# STM32G4_4008_brushless_motor.net
KiCad netlist of a schematic drawn in Altium Designer
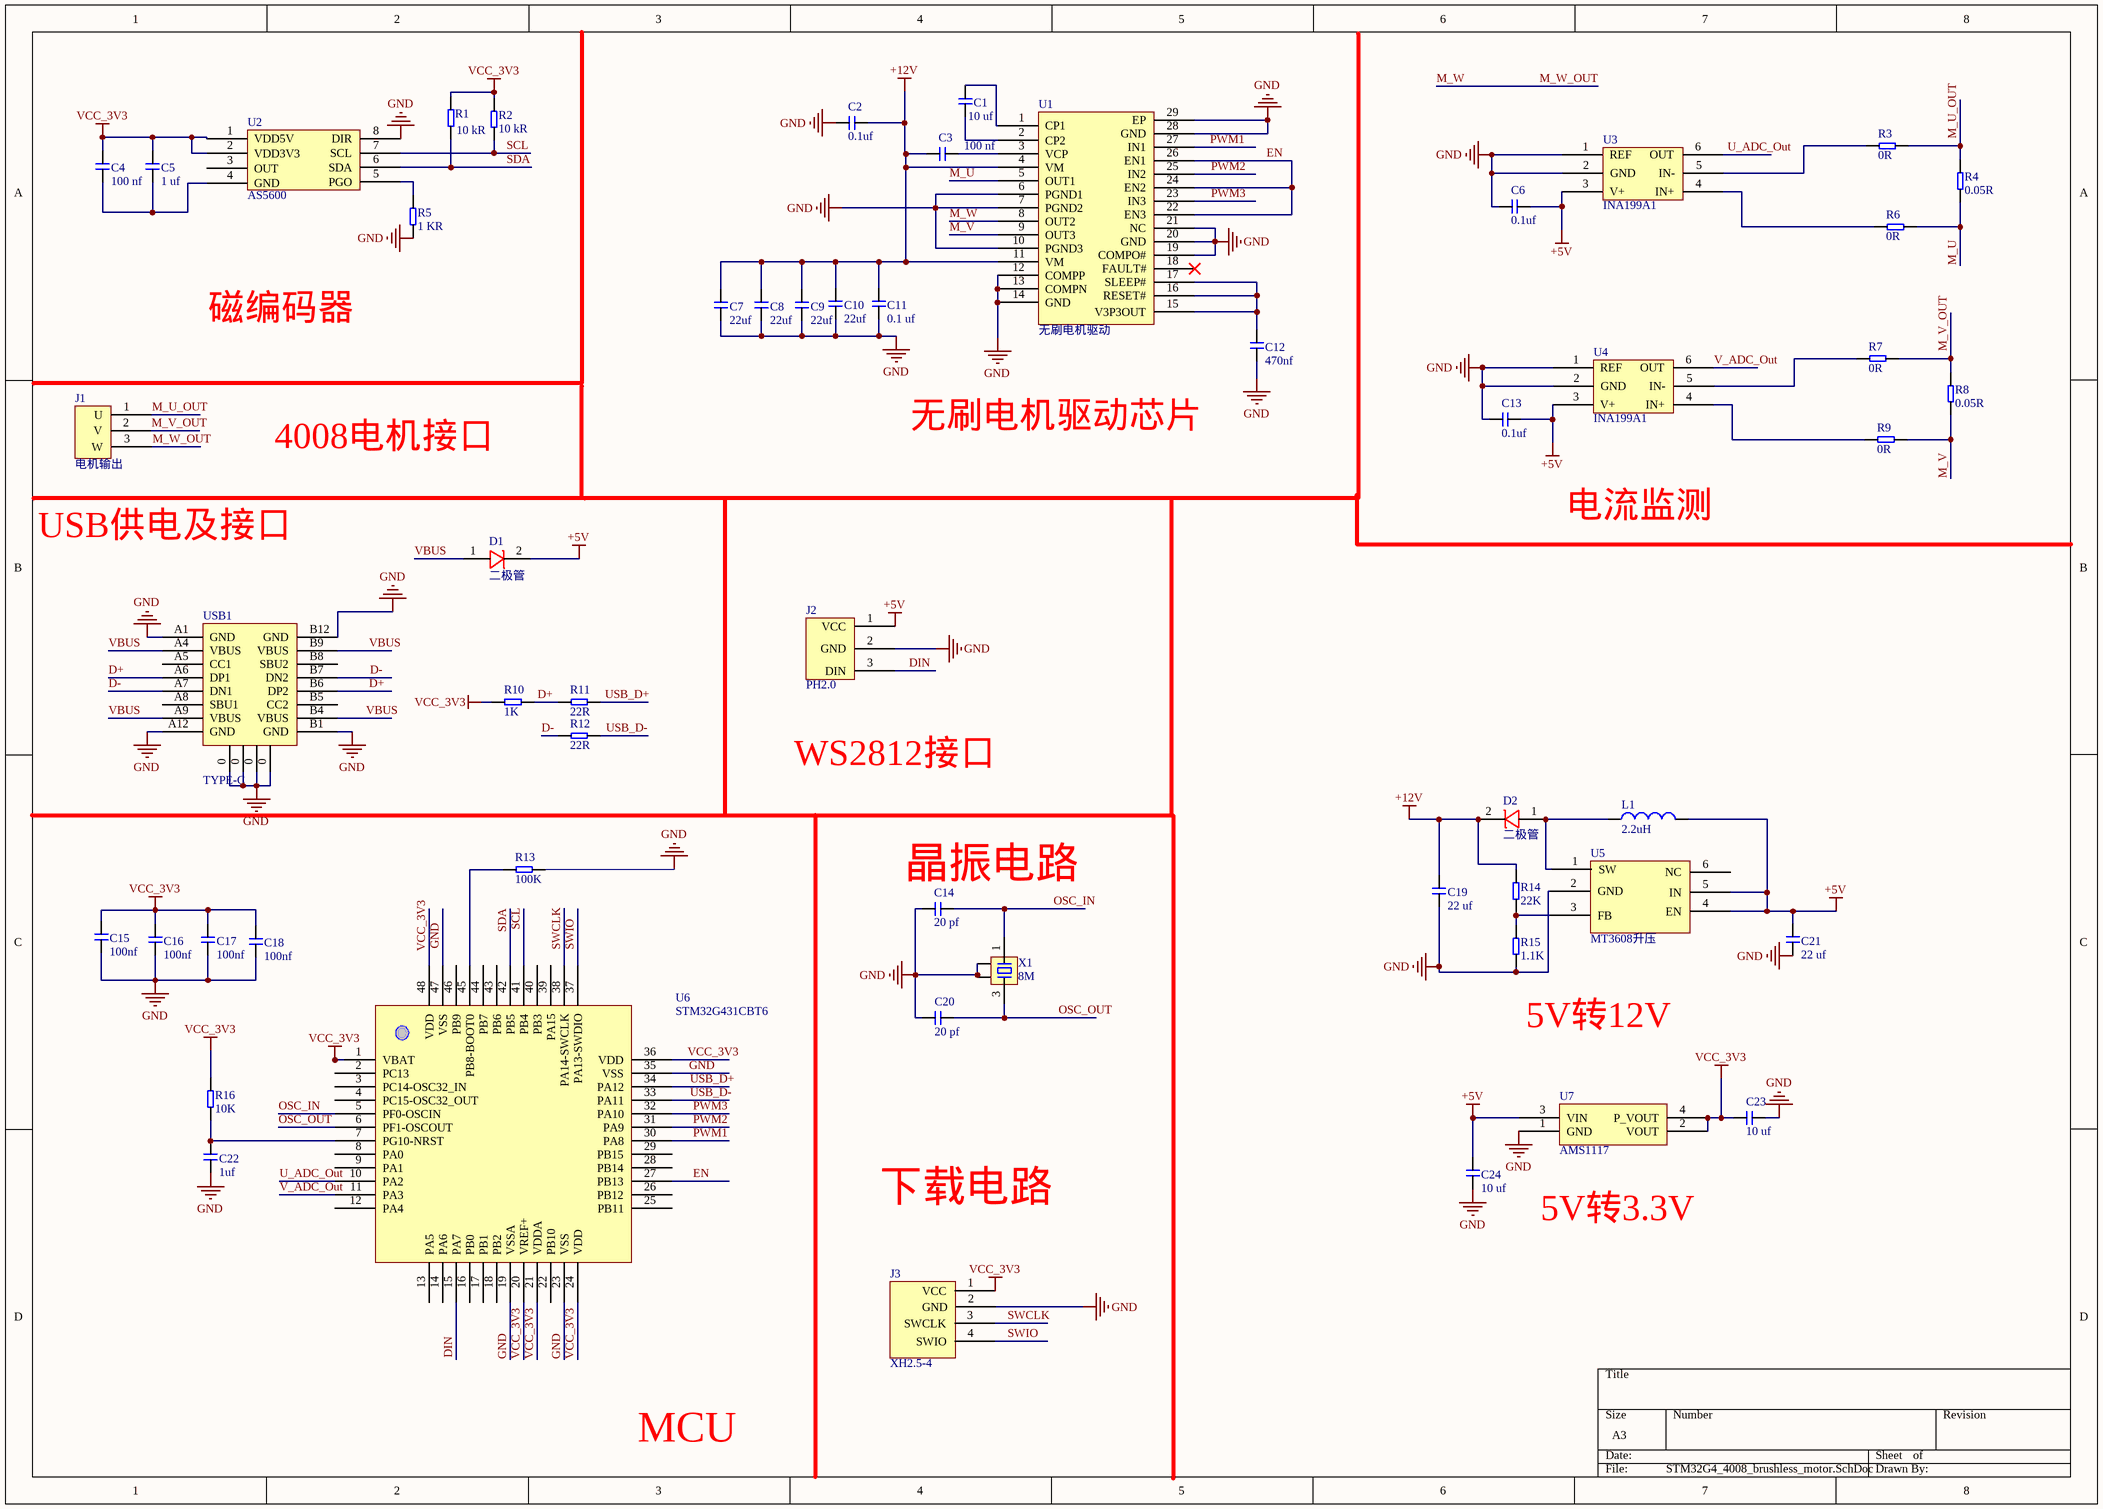
[diagram p0: STM32G4_4008_brushless_motor.SchDoc]

(export (version "E")
  (design (tool "Eeschema 10.0.6"))
  (components
    (comp (ref "C1")
      (value "10 uf")
      (footprint "C 0603")
      (description "电容0603")
      (libsource (lib "Schlib1") (part "电容C"))
    )
    (comp (ref "C2")
      (value "0.1uf")
      (footprint "C 0603")
      (description "电容0603")
      (libsource (lib "Schlib1") (part "电容C"))
    )
    (comp (ref "C3")
      (value "100 nf")
      (footprint "C 0603")
      (description "电容0603")
      (libsource (lib "Schlib1") (part "电容C"))
    )
    (comp (ref "C4")
      (value "100 nf")
      (footprint "C 0603")
      (description "电容0603")
      (libsource (lib "Schlib1") (part "电容C"))
    )
    (comp (ref "C5")
      (value "1 uf")
      (footprint "C 0603")
      (description "电容0603")
      (libsource (lib "Schlib1") (part "电容C"))
    )
    (comp (ref "C6")
      (value "0.1uf")
      (footprint "C 0603")
      (description "电容0603")
      (libsource (lib "Schlib1") (part "电容C"))
    )
    (comp (ref "C7")
      (value "22uf")
      (footprint "C 0603")
      (description "电容0603")
      (libsource (lib "Schlib1") (part "电容C"))
    )
    (comp (ref "C8")
      (value "22uf")
      (footprint "C 0603")
      (description "电容0603")
      (libsource (lib "Schlib1") (part "电容C"))
    )
    (comp (ref "C9")
      (value "22uf")
      (footprint "C 0603")
      (description "电容0603")
      (libsource (lib "Schlib1") (part "电容C"))
    )
    (comp (ref "C10")
      (value "22uf")
      (footprint "C 0603")
      (description "电容0603")
      (libsource (lib "Schlib1") (part "电容C"))
    )
    (comp (ref "C11")
      (value "0.1 uf")
      (footprint "C 0603")
      (description "电容0603")
      (libsource (lib "Schlib1") (part "电容C"))
    )
    (comp (ref "C12")
      (value "470nf")
      (footprint "C 0603")
      (description "电容0603")
      (libsource (lib "Schlib1") (part "电容C"))
    )
    (comp (ref "C13")
      (value "0.1uf")
      (footprint "C 0603")
      (description "电容0603")
      (libsource (lib "Schlib1") (part "电容C"))
    )
    (comp (ref "C14")
      (value "20 pf")
      (footprint "C 0603")
      (description "电容0603")
      (libsource (lib "Bottom_MCU_Control") (part "电容C"))
    )
    (comp (ref "C15")
      (value "100nf")
      (footprint "C 0603")
      (description "电容0603")
      (libsource (lib "Bottom_MCU_Control") (part "电容C"))
    )
    (comp (ref "C16")
      (value "100nf")
      (footprint "C 0603")
      (description "电容0603")
      (libsource (lib "Bottom_MCU_Control") (part "电容C"))
    )
    (comp (ref "C17")
      (value "100nf")
      (footprint "C 0603")
      (description "电容0603")
      (libsource (lib "Bottom_MCU_Control") (part "电容C"))
    )
    (comp (ref "C18")
      (value "100nf")
      (footprint "C 0603")
      (description "电容0603")
      (libsource (lib "Bottom_MCU_Control") (part "电容C"))
    )
    (comp (ref "C19")
      (value "22 uf")
      (footprint "C 0603")
      (description "电容0603")
      (libsource (lib "ValentineHP") (part "电容C"))
    )
    (comp (ref "C20")
      (value "20 pf")
      (footprint "C 0603")
      (description "电容0603")
      (libsource (lib "Bottom_MCU_Control") (part "电容C"))
    )
    (comp (ref "C21")
      (value "22 uf")
      (footprint "C 0603")
      (description "电容0603")
      (libsource (lib "ValentineHP") (part "电容C"))
    )
    (comp (ref "C22")
      (value "1uf")
      (footprint "C 0603")
      (description "电容0603")
      (libsource (lib "Bottom_MCU_Control") (part "电容C"))
    )
    (comp (ref "C23")
      (value "10 uf")
      (footprint "C 0603")
      (description "电容0603")
      (libsource (lib "ValentineHP") (part "电容C"))
    )
    (comp (ref "C24")
      (value "10 uf")
      (footprint "C 0603")
      (description "电容0603")
      (libsource (lib "ValentineHP") (part "电容C"))
    )
    (comp (ref "D1") (value "二极管") (footprint "SMA") (libsource (lib "原理图库") (part "二极管")))
    (comp (ref "D2") (value "二极管") (footprint "SMA") (libsource (lib "Schlib1") (part "二极管")))
    (comp (ref "J1")
      (value "电机输出")
      (footprint "SH1.0-WT-3P")
      (libsource (lib "STM32G4_4008_brushless_motor") (part "电机输出"))
    )
    (comp (ref "J2") (value "PH2.0") (footprint "PH2.0-WI-3P") (libsource (lib "WS2812Ring") (part "PH2.0")))
    (comp (ref "J3")
      (value "XH2.5-4")
      (footprint "HDR2.54-M-LI-4P")
      (libsource (lib "STM32G4_4008_brushless_motor") (part "XH2.5-4"))
    )
    (comp (ref "L1")
      (value "2.2uH")
      (footprint "L-SMD-0630")
      (description "小功率贴片电感")
      (fields (field (name "版权归属") "源创客"))
      (libsource (lib "Schlib1") (part "L"))
    )
    (comp (ref "R1")
      (value "10 kR")
      (footprint "R 0603")
      (description "电阻0603")
      (libsource (lib "Schlib1") (part "电阻R"))
    )
    (comp (ref "R2")
      (value "10 kR")
      (footprint "R 0603")
      (description "电阻0603")
      (libsource (lib "Schlib1") (part "电阻R"))
    )
    (comp (ref "R3")
      (value "0R")
      (footprint "R 0603")
      (description "电阻0603")
      (libsource (lib "Schlib1") (part "电阻R"))
    )
    (comp (ref "R4")
      (value "0.05R")
      (footprint "R 2512-HP_L")
      (description "电阻0603")
      (libsource (lib "Schlib1") (part "电阻R"))
    )
    (comp (ref "R5")
      (value "1 KR")
      (footprint "R 0603")
      (description "电阻0603")
      (libsource (lib "Schlib1") (part "电阻R"))
    )
    (comp (ref "R6")
      (value "0R")
      (footprint "R 0603")
      (description "电阻0603")
      (libsource (lib "Schlib1") (part "电阻R"))
    )
    (comp (ref "R7")
      (value "0R")
      (footprint "R 0603")
      (description "电阻0603")
      (libsource (lib "Schlib1") (part "电阻R"))
    )
    (comp (ref "R8")
      (value "0.05R")
      (footprint "R 2512-HP_L")
      (description "电阻0603")
      (libsource (lib "Schlib1") (part "电阻R"))
    )
    (comp (ref "R9")
      (value "0R")
      (footprint "R 0603")
      (description "电阻0603")
      (libsource (lib "Schlib1") (part "电阻R"))
    )
    (comp (ref "R10")
      (value "1K")
      (footprint "R 0603")
      (description "电阻0603")
      (libsource (lib "Bottom_MCU_Control") (part "电阻R"))
    )
    (comp (ref "R11")
      (value "22R")
      (footprint "R 0603")
      (description "电阻0603")
      (libsource (lib "Bottom_MCU_Control") (part "电阻R"))
    )
    (comp (ref "R12")
      (value "22R")
      (footprint "R 0603")
      (description "电阻0603")
      (libsource (lib "Bottom_MCU_Control") (part "电阻R"))
    )
    (comp (ref "R13")
      (value "100K")
      (footprint "R 0603")
      (description "电阻0603")
      (libsource (lib "Bottom_MCU_Control") (part "电阻R"))
    )
    (comp (ref "R14")
      (value "22K")
      (footprint "R 0603")
      (description "电阻0603")
      (libsource (lib "Schlib1") (part "电阻R"))
    )
    (comp (ref "R15")
      (value "1.1K")
      (footprint "R 0603")
      (description "电阻0603")
      (libsource (lib "Schlib1") (part "电阻R"))
    )
    (comp (ref "R16")
      (value "10K")
      (footprint "R 0603")
      (description "电阻0603")
      (libsource (lib "Bottom_MCU_Control") (part "电阻R"))
    )
    (comp (ref "U1") (value "无刷电机驱动") (footprint "TSSOP28_n") (libsource (lib "Schlib1") (part "DRV8313")))
    (comp (ref "U2") (value "AS5600") (footprint "SOP8_N") (libsource (lib "Schlib1") (part "AS5600")))
    (comp (ref "U3")
      (value "INA199A1")
      (footprint "SOT36-3N")
      (description "电流检测")
      (libsource (lib "4008_brushless_motor") (part "INA199A1"))
    )
    (comp (ref "U4")
      (value "INA199A1")
      (footprint "SOT36-3N")
      (description "电流检测")
      (libsource (lib "") (part "INA199A1_1"))
    )
    (comp (ref "U5") (value "MT3608升压") (footprint "SOT23-6L") (libsource (lib "Schlib1") (part "MT3608")))
    (comp (ref "U6")
      (value "STM32G431CBT6")
      (footprint "TQFP48 7x7_L")
      (libsource (lib "STM32G4_4008_brushless_motor") (part "STM32G431CBT6"))
    )
    (comp (ref "U7")
      (value "AMS1117")
      (footprint "SOT223_N")
      (description "电平转换模块")
      (libsource (lib "ValentineHP") (part "5V转3.3V"))
    )
    (comp (ref "USB1")
      (value "TYPE-C")
      (footprint "USB-C-SMD_TYPE-C-USB-5")
      (description "type-c")
      (libsource (lib "ValentineHP") (part "TYPE-C"))
    )
    (comp (ref "X1")
      (value "8M")
      (footprint "OSC 3225-4P")
      (description "4脚无源晶振")
      (fields (field (name "版权归属") "源创客"))
      (libsource (lib "STM32G4_4008_brushless_motor") (part "XTAL-4P"))
    )
  )
  (nets
    (net (code "1") (name "+5V") (class "Default")
      (node (ref "C13") (pin "2") (pinfunction "2_2") (pintype "passive"))
      (node (ref "C21") (pin "1") (pinfunction "1_1") (pintype "passive"))
      (node (ref "C24") (pin "1") (pinfunction "1_1") (pintype "passive"))
      (node (ref "C6") (pin "2") (pinfunction "2_2") (pintype "passive"))
      (node (ref "D1") (pin "2") (pinfunction "2_2") (pintype "passive"))
      (node (ref "J2") (pin "1") (pinfunction "VCC_1") (pintype "passive"))
      (node (ref "L1") (pin "2") (pinfunction "2_2") (pintype "passive"))
      (node (ref "U3") (pin "3") (pinfunction "V+_3") (pintype "passive"))
      (node (ref "U4") (pin "3") (pinfunction "V+_3") (pintype "passive"))
      (node (ref "U5") (pin "4") (pinfunction "EN_4") (pintype "passive"))
      (node (ref "U5") (pin "5") (pinfunction "IN_5") (pintype "passive"))
      (node (ref "U7") (pin "3") (pinfunction "VIN_3") (pintype "passive"))
    )
    (net (code "2") (name "+12V") (class "Default")
      (node (ref "C10") (pin "1") (pinfunction "1_1") (pintype "passive"))
      (node (ref "C11") (pin "1") (pinfunction "1_1") (pintype "passive"))
      (node (ref "C19") (pin "1") (pinfunction "1_1") (pintype "passive"))
      (node (ref "C2") (pin "2") (pinfunction "2_2") (pintype "passive"))
      (node (ref "C3") (pin "2") (pinfunction "2_2") (pintype "passive"))
      (node (ref "C7") (pin "1") (pinfunction "1_1") (pintype "passive"))
      (node (ref "C8") (pin "1") (pinfunction "1_1") (pintype "passive"))
      (node (ref "C9") (pin "1") (pinfunction "1_1") (pintype "passive"))
      (node (ref "D2") (pin "2") (pinfunction "2_2") (pintype "passive"))
      (node (ref "R14") (pin "2") (pinfunction "2_2") (pintype "passive"))
      (node (ref "U1") (pin "11") (pinfunction "VM_11") (pintype "passive"))
      (node (ref "U1") (pin "4") (pinfunction "VM_4") (pintype "passive"))
    )
    (net (code "3") (name "/D+") (class "Default")
      (node (ref "R10") (pin "1") (pinfunction "1_1") (pintype "passive"))
      (node (ref "R11") (pin "1") (pinfunction "1_1") (pintype "passive"))
      (node (ref "USB1") (pin "A6") (pinfunction "DP1_A6") (pintype "passive"))
      (node (ref "USB1") (pin "B6") (pinfunction "DP2_B6") (pintype "passive"))
    )
    (net (code "4") (name "/D-") (class "Default")
      (node (ref "R12") (pin "1") (pinfunction "1_1") (pintype "passive"))
      (node (ref "USB1") (pin "A7") (pinfunction "DN1_A7") (pintype "passive"))
      (node (ref "USB1") (pin "B7") (pinfunction "DN2_B7") (pintype "passive"))
    )
    (net (code "5") (name "/DIN") (class "Default")
      (node (ref "J2") (pin "3") (pinfunction "DIN_3") (pintype "passive"))
      (node (ref "U6") (pin "15") (pinfunction "PA7_15") (pintype "passive"))
    )
    (net (code "6") (name "/EN") (class "Default")
      (node (ref "U1") (pin "22") (pinfunction "EN3_22") (pintype "passive"))
      (node (ref "U1") (pin "24") (pinfunction "EN2_24") (pintype "passive"))
      (node (ref "U1") (pin "26") (pinfunction "EN1_26") (pintype "passive"))
      (node (ref "U6") (pin "27") (pinfunction "PB13_27") (pintype "passive"))
    )
    (net (code "7") (name "/M_U") (class "Default")
      (node (ref "R4") (pin "2") (pinfunction "2_2") (pintype "passive"))
      (node (ref "R6") (pin "1") (pinfunction "1_1") (pintype "passive"))
      (node (ref "U1") (pin "5") (pinfunction "OUT1_5") (pintype "passive"))
    )
    (net (code "8") (name "/M_U_OUT") (class "Default")
      (node (ref "J1") (pin "1") (pinfunction "U_1") (pintype "passive"))
      (node (ref "R3") (pin "1") (pinfunction "1_1") (pintype "passive"))
      (node (ref "R4") (pin "1") (pinfunction "1_1") (pintype "passive"))
    )
    (net (code "9") (name "/M_V") (class "Default")
      (node (ref "R8") (pin "2") (pinfunction "2_2") (pintype "passive"))
      (node (ref "R9") (pin "1") (pinfunction "1_1") (pintype "passive"))
      (node (ref "U1") (pin "9") (pinfunction "OUT3_9") (pintype "passive"))
    )
    (net (code "10") (name "/M_V_OUT") (class "Default")
      (node (ref "J1") (pin "2") (pinfunction "V_2") (pintype "passive"))
      (node (ref "R7") (pin "1") (pinfunction "1_1") (pintype "passive"))
      (node (ref "R8") (pin "1") (pinfunction "1_1") (pintype "passive"))
    )
    (net (code "11") (name "/M_W") (class "Default")
      (node (ref "J1") (pin "3") (pinfunction "W_3") (pintype "passive"))
      (node (ref "U1") (pin "8") (pinfunction "OUT2_8") (pintype "passive"))
    )
    (net (code "12") (name "/OSC_IN") (class "Default")
      (node (ref "C14") (pin "1") (pinfunction "1_1") (pintype "passive"))
      (node (ref "U6") (pin "5") (pinfunction "PF0-OSCIN_5") (pintype "passive"))
      (node (ref "X1") (pin "1") (pinfunction "1_1") (pintype "passive"))
    )
    (net (code "13") (name "/OSC_OUT") (class "Default")
      (node (ref "C20") (pin "1") (pinfunction "1_1") (pintype "passive"))
      (node (ref "U6") (pin "6") (pinfunction "PF1-OSCOUT_6") (pintype "passive"))
      (node (ref "X1") (pin "3") (pinfunction "3_3") (pintype "passive"))
    )
    (net (code "14") (name "/PWM1") (class "Default")
      (node (ref "U1") (pin "27") (pinfunction "IN1_27") (pintype "passive"))
      (node (ref "U6") (pin "30") (pinfunction "PA8_30") (pintype "passive"))
    )
    (net (code "15") (name "/PWM2") (class "Default")
      (node (ref "U1") (pin "25") (pinfunction "IN2_25") (pintype "passive"))
      (node (ref "U6") (pin "31") (pinfunction "PA9_31") (pintype "passive"))
    )
    (net (code "16") (name "/PWM3") (class "Default")
      (node (ref "U1") (pin "23") (pinfunction "IN3_23") (pintype "passive"))
      (node (ref "U6") (pin "32") (pinfunction "PA10_32") (pintype "passive"))
    )
    (net (code "17") (name "/SCL") (class "Default")
      (node (ref "R2") (pin "1") (pinfunction "1_1") (pintype "passive"))
      (node (ref "U2") (pin "7") (pinfunction "SCL_7") (pintype "passive"))
      (node (ref "U6") (pin "41") (pinfunction "PB4_41") (pintype "passive"))
    )
    (net (code "18") (name "/SDA") (class "Default")
      (node (ref "R1") (pin "1") (pinfunction "1_1") (pintype "passive"))
      (node (ref "U2") (pin "6") (pinfunction "SDA_6") (pintype "passive"))
      (node (ref "U6") (pin "42") (pinfunction "PB5_42") (pintype "passive"))
    )
    (net (code "19") (name "/SWCLK") (class "Default")
      (node (ref "J3") (pin "3") (pinfunction "SWCLK_3") (pintype "passive"))
      (node (ref "U6") (pin "38") (pinfunction "PA14-SWCLK_38") (pintype "passive"))
    )
    (net (code "20") (name "/SWIO") (class "Default")
      (node (ref "J3") (pin "4") (pinfunction "SWIO_4") (pintype "passive"))
      (node (ref "U6") (pin "37") (pinfunction "PA13-SWDIO_37") (pintype "passive"))
    )
    (net (code "21") (name "/USB_D+") (class "Default")
      (node (ref "R11") (pin "2") (pinfunction "2_2") (pintype "passive"))
      (node (ref "U6") (pin "34") (pinfunction "PA12_34") (pintype "passive"))
    )
    (net (code "22") (name "/USB_D-") (class "Default")
      (node (ref "R12") (pin "2") (pinfunction "2_2") (pintype "passive"))
      (node (ref "U6") (pin "33") (pinfunction "PA11_33") (pintype "passive"))
    )
    (net (code "23") (name "/U_ADC_Out") (class "Default")
      (node (ref "U3") (pin "6") (pinfunction "OUT_6") (pintype "passive"))
      (node (ref "U6") (pin "10") (pinfunction "PA2_10") (pintype "passive"))
    )
    (net (code "24") (name "/VBUS") (class "Default")
      (node (ref "D1") (pin "1") (pinfunction "1_1") (pintype "passive"))
      (node (ref "USB1") (pin "A4") (pinfunction "VBUS_A4") (pintype "passive"))
      (node (ref "USB1") (pin "A9") (pinfunction "VBUS_A9") (pintype "passive"))
      (node (ref "USB1") (pin "B4") (pinfunction "VBUS_B4") (pintype "passive"))
      (node (ref "USB1") (pin "B9") (pinfunction "VBUS_B9") (pintype "passive"))
    )
    (net (code "25") (name "/V_ADC_Out") (class "Default")
      (node (ref "U4") (pin "6") (pinfunction "OUT_6") (pintype "passive"))
      (node (ref "U6") (pin "11") (pinfunction "PA3_11") (pintype "passive"))
    )
    (net (code "26") (name "GND") (class "Default")
      (node (ref "C10") (pin "2") (pinfunction "2_2") (pintype "passive"))
      (node (ref "C11") (pin "2") (pinfunction "2_2") (pintype "passive"))
      (node (ref "C12") (pin "2") (pinfunction "2_2") (pintype "passive"))
      (node (ref "C13") (pin "1") (pinfunction "1_1") (pintype "passive"))
      (node (ref "C14") (pin "2") (pinfunction "2_2") (pintype "passive"))
      (node (ref "C15") (pin "2") (pinfunction "2_2") (pintype "passive"))
      (node (ref "C16") (pin "2") (pinfunction "2_2") (pintype "passive"))
      (node (ref "C17") (pin "2") (pinfunction "2_2") (pintype "passive"))
      (node (ref "C18") (pin "2") (pinfunction "2_2") (pintype "passive"))
      (node (ref "C19") (pin "2") (pinfunction "2_2") (pintype "passive"))
      (node (ref "C2") (pin "1") (pinfunction "1_1") (pintype "passive"))
      (node (ref "C20") (pin "2") (pinfunction "2_2") (pintype "passive"))
      (node (ref "C21") (pin "2") (pinfunction "2_2") (pintype "passive"))
      (node (ref "C22") (pin "2") (pinfunction "2_2") (pintype "passive"))
      (node (ref "C23") (pin "1") (pinfunction "1_1") (pintype "passive"))
      (node (ref "C24") (pin "2") (pinfunction "2_2") (pintype "passive"))
      (node (ref "C6") (pin "1") (pinfunction "1_1") (pintype "passive"))
      (node (ref "C7") (pin "2") (pinfunction "2_2") (pintype "passive"))
      (node (ref "C8") (pin "2") (pinfunction "2_2") (pintype "passive"))
      (node (ref "C9") (pin "2") (pinfunction "2_2") (pintype "passive"))
      (node (ref "J2") (pin "2") (pinfunction "GND_2") (pintype "passive"))
      (node (ref "J3") (pin "2") (pinfunction "GND_2") (pintype "passive"))
      (node (ref "R13") (pin "2") (pinfunction "2_2") (pintype "passive"))
      (node (ref "R15") (pin "1") (pinfunction "1_1") (pintype "passive"))
      (node (ref "R5") (pin "1") (pinfunction "1_1") (pintype "passive"))
      (node (ref "U1") (pin "10") (pinfunction "PGND3_10") (pintype "passive"))
      (node (ref "U1") (pin "12") (pinfunction "COMPP_12") (pintype "passive"))
      (node (ref "U1") (pin "13") (pinfunction "COMPN_13") (pintype "passive"))
      (node (ref "U1") (pin "14") (pinfunction "GND_14") (pintype "passive"))
      (node (ref "U1") (pin "19") (pinfunction "COMPO#_19") (pintype "passive"))
      (node (ref "U1") (pin "20") (pinfunction "GND_20") (pintype "passive"))
      (node (ref "U1") (pin "21") (pinfunction "NC_21") (pintype "passive"))
      (node (ref "U1") (pin "28") (pinfunction "GND_28") (pintype "passive"))
      (node (ref "U1") (pin "29") (pinfunction "EP_29") (pintype "passive"))
      (node (ref "U1") (pin "6") (pinfunction "PGND1_6") (pintype "passive"))
      (node (ref "U1") (pin "7") (pinfunction "PGND2_7") (pintype "passive"))
      (node (ref "U2") (pin "8") (pinfunction "DIR_8") (pintype "passive"))
      (node (ref "U3") (pin "1") (pinfunction "REF_1") (pintype "passive"))
      (node (ref "U3") (pin "2") (pinfunction "GND_2") (pintype "passive"))
      (node (ref "U4") (pin "1") (pinfunction "REF_1") (pintype "passive"))
      (node (ref "U4") (pin "2") (pinfunction "GND_2") (pintype "passive"))
      (node (ref "U5") (pin "2") (pinfunction "GND_2") (pintype "passive"))
      (node (ref "U6") (pin "19") (pinfunction "VSSA_19") (pintype "passive"))
      (node (ref "U6") (pin "23") (pinfunction "VSS_23") (pintype "passive"))
      (node (ref "U6") (pin "35") (pinfunction "VSS_35") (pintype "passive"))
      (node (ref "U6") (pin "47") (pinfunction "VSS_47") (pintype "passive"))
      (node (ref "U7") (pin "1") (pinfunction "GND_1") (pintype "passive"))
      (node (ref "USB1") (pin "0") (pinfunction "4_0") (pintype "passive"))
      (node (ref "USB1") (pin "A1") (pinfunction "GND_A1") (pintype "passive"))
      (node (ref "USB1") (pin "A12") (pinfunction "GND_A12") (pintype "passive"))
      (node (ref "USB1") (pin "B1") (pinfunction "GND_B1") (pintype "passive"))
      (node (ref "USB1") (pin "B12") (pinfunction "GND_B12") (pintype "passive"))
      (node (ref "X1") (pin "2") (pinfunction "2_2") (pintype "passive"))
      (node (ref "X1") (pin "4") (pinfunction "4_4") (pintype "passive"))
    )
    (net (code "27") (name "Net-(U1-CP1)") (class "Default")
      (node (ref "C1") (pin "1") (pinfunction "1_1") (pintype "passive"))
      (node (ref "U1") (pin "1") (pinfunction "CP1_1") (pintype "passive"))
    )
    (net (code "28") (name "Net-(U1-CP2)") (class "Default")
      (node (ref "C1") (pin "2") (pinfunction "2_2") (pintype "passive"))
      (node (ref "U1") (pin "2") (pinfunction "CP2_2") (pintype "passive"))
    )
    (net (code "29") (name "Net-(U1-RESET#)") (class "Default")
      (node (ref "C12") (pin "1") (pinfunction "1_1") (pintype "passive"))
      (node (ref "U1") (pin "15") (pinfunction "V3P3OUT_15") (pintype "passive"))
      (node (ref "U1") (pin "16") (pinfunction "RESET#_16") (pintype "passive"))
      (node (ref "U1") (pin "17") (pinfunction "SLEEP#_17") (pintype "passive"))
    )
    (net (code "30") (name "Net-(U1-VCP)") (class "Default")
      (node (ref "C3") (pin "1") (pinfunction "1_1") (pintype "passive"))
      (node (ref "U1") (pin "3") (pinfunction "VCP_3") (pintype "passive"))
    )
    (net (code "31") (name "Net-(U2-GND)") (class "Default")
      (node (ref "C4") (pin "2") (pinfunction "2_2") (pintype "passive"))
      (node (ref "C5") (pin "2") (pinfunction "2_2") (pintype "passive"))
      (node (ref "U2") (pin "4") (pinfunction "GND_4") (pintype "passive"))
    )
    (net (code "32") (name "Net-(U2-PGO)") (class "Default")
      (node (ref "R5") (pin "2") (pinfunction "2_2") (pintype "passive"))
      (node (ref "U2") (pin "5") (pinfunction "PGO_5") (pintype "passive"))
    )
    (net (code "33") (name "Net-(U3-IN+)") (class "Default")
      (node (ref "R6") (pin "2") (pinfunction "2_2") (pintype "passive"))
      (node (ref "U3") (pin "4") (pinfunction "IN+_4") (pintype "passive"))
    )
    (net (code "34") (name "Net-(U3-IN-)") (class "Default")
      (node (ref "R3") (pin "2") (pinfunction "2_2") (pintype "passive"))
      (node (ref "U3") (pin "5") (pinfunction "IN-_5") (pintype "passive"))
    )
    (net (code "35") (name "Net-(U4-IN+)") (class "Default")
      (node (ref "R9") (pin "2") (pinfunction "2_2") (pintype "passive"))
      (node (ref "U4") (pin "4") (pinfunction "IN+_4") (pintype "passive"))
    )
    (net (code "36") (name "Net-(U4-IN-)") (class "Default")
      (node (ref "R7") (pin "2") (pinfunction "2_2") (pintype "passive"))
      (node (ref "U4") (pin "5") (pinfunction "IN-_5") (pintype "passive"))
    )
    (net (code "37") (name "Net-(U5-FB)") (class "Default")
      (node (ref "R14") (pin "1") (pinfunction "1_1") (pintype "passive"))
      (node (ref "R15") (pin "2") (pinfunction "2_2") (pintype "passive"))
      (node (ref "U5") (pin "3") (pinfunction "FB_3") (pintype "passive"))
    )
    (net (code "38") (name "Net-(U5-SW)") (class "Default")
      (node (ref "D2") (pin "1") (pinfunction "1_1") (pintype "passive"))
      (node (ref "L1") (pin "1") (pinfunction "1_1") (pintype "passive"))
      (node (ref "U5") (pin "1") (pinfunction "SW_1") (pintype "passive"))
    )
    (net (code "39") (name "Net-(U6-PB8-BOOT0)") (class "Default")
      (node (ref "R13") (pin "1") (pinfunction "1_1") (pintype "passive"))
      (node (ref "U6") (pin "45") (pinfunction "PB8-BOOT0_45") (pintype "passive"))
    )
    (net (code "40") (name "Net-(U6-PG10-NRST)") (class "Default")
      (node (ref "C22") (pin "1") (pinfunction "1_1") (pintype "passive"))
      (node (ref "R16") (pin "2") (pinfunction "2_2") (pintype "passive"))
      (node (ref "U6") (pin "7") (pinfunction "PG10-NRST_7") (pintype "passive"))
    )
    (net (code "41") (name "VCC_3V3") (class "Default")
      (node (ref "C15") (pin "1") (pinfunction "1_1") (pintype "passive"))
      (node (ref "C16") (pin "1") (pinfunction "1_1") (pintype "passive"))
      (node (ref "C17") (pin "1") (pinfunction "1_1") (pintype "passive"))
      (node (ref "C18") (pin "1") (pinfunction "1_1") (pintype "passive"))
      (node (ref "C23") (pin "2") (pinfunction "2_2") (pintype "passive"))
      (node (ref "C4") (pin "1") (pinfunction "1_1") (pintype "passive"))
      (node (ref "C5") (pin "1") (pinfunction "1_1") (pintype "passive"))
      (node (ref "J3") (pin "1") (pinfunction "VCC_1") (pintype "passive"))
      (node (ref "R1") (pin "2") (pinfunction "2_2") (pintype "passive"))
      (node (ref "R10") (pin "2") (pinfunction "2_2") (pintype "passive"))
      (node (ref "R16") (pin "1") (pinfunction "1_1") (pintype "passive"))
      (node (ref "R2") (pin "2") (pinfunction "2_2") (pintype "passive"))
      (node (ref "U2") (pin "1") (pinfunction "VDD5V_1") (pintype "passive"))
      (node (ref "U2") (pin "2") (pinfunction "VDD3V3_2") (pintype "passive"))
      (node (ref "U6") (pin "1") (pinfunction "VBAT_1") (pintype "passive"))
      (node (ref "U6") (pin "20") (pinfunction "VREF+_20") (pintype "passive"))
      (node (ref "U6") (pin "21") (pinfunction "VDDA_21") (pintype "passive"))
      (node (ref "U6") (pin "24") (pinfunction "VDD_24") (pintype "passive"))
      (node (ref "U6") (pin "36") (pinfunction "VDD_36") (pintype "passive"))
      (node (ref "U6") (pin "48") (pinfunction "VDD_48") (pintype "passive"))
      (node (ref "U7") (pin "2") (pinfunction "VOUT_2") (pintype "passive"))
      (node (ref "U7") (pin "4") (pinfunction "P_VOUT_4") (pintype "passive"))
    )
    (net (code "42") (name "unconnected-(U1-FAULT#-Pad18)") (class "Default")
      (node (ref "U1") (pin "18") (pinfunction "FAULT#_18") (pintype "passive+no_connect"))
    )
    (net (code "43") (name "unconnected-(U2-OUT-Pad3)") (class "Default")
      (node (ref "U2") (pin "3") (pinfunction "OUT_3") (pintype "passive"))
    )
    (net (code "44") (name "unconnected-(U5-NC-Pad6)") (class "Default")
      (node (ref "U5") (pin "6") (pinfunction "NC_6") (pintype "passive"))
    )
    (net (code "45") (name "unconnected-(U6-PA0-Pad8)") (class "Default")
      (node (ref "U6") (pin "8") (pinfunction "PA0_8") (pintype "passive"))
    )
    (net (code "46") (name "unconnected-(U6-PA1-Pad9)") (class "Default")
      (node (ref "U6") (pin "9") (pinfunction "PA1_9") (pintype "passive"))
    )
    (net (code "47") (name "unconnected-(U6-PA4-Pad12)") (class "Default")
      (node (ref "U6") (pin "12") (pinfunction "PA4_12") (pintype "passive"))
    )
    (net (code "48") (name "unconnected-(U6-PA5-Pad13)") (class "Default")
      (node (ref "U6") (pin "13") (pinfunction "PA5_13") (pintype "passive"))
    )
    (net (code "49") (name "unconnected-(U6-PA6-Pad14)") (class "Default")
      (node (ref "U6") (pin "14") (pinfunction "PA6_14") (pintype "passive"))
    )
    (net (code "50") (name "unconnected-(U6-PA15-Pad39)") (class "Default")
      (node (ref "U6") (pin "39") (pinfunction "PA15_39") (pintype "passive"))
    )
    (net (code "51") (name "unconnected-(U6-PB0-Pad16)") (class "Default")
      (node (ref "U6") (pin "16") (pinfunction "PB0_16") (pintype "passive"))
    )
    (net (code "52") (name "unconnected-(U6-PB1-Pad17)") (class "Default")
      (node (ref "U6") (pin "17") (pinfunction "PB1_17") (pintype "passive"))
    )
    (net (code "53") (name "unconnected-(U6-PB2-Pad18)") (class "Default")
      (node (ref "U6") (pin "18") (pinfunction "PB2_18") (pintype "passive"))
    )
    (net (code "54") (name "unconnected-(U6-PB3-Pad40)") (class "Default")
      (node (ref "U6") (pin "40") (pinfunction "PB3_40") (pintype "passive"))
    )
    (net (code "55") (name "unconnected-(U6-PB6-Pad43)") (class "Default")
      (node (ref "U6") (pin "43") (pinfunction "PB6_43") (pintype "passive"))
    )
    (net (code "56") (name "unconnected-(U6-PB7-Pad44)") (class "Default")
      (node (ref "U6") (pin "44") (pinfunction "PB7_44") (pintype "passive"))
    )
    (net (code "57") (name "unconnected-(U6-PB9-Pad46)") (class "Default")
      (node (ref "U6") (pin "46") (pinfunction "PB9_46") (pintype "passive"))
    )
    (net (code "58") (name "unconnected-(U6-PB10-Pad22)") (class "Default")
      (node (ref "U6") (pin "22") (pinfunction "PB10_22") (pintype "passive"))
    )
    (net (code "59") (name "unconnected-(U6-PB11-Pad25)") (class "Default")
      (node (ref "U6") (pin "25") (pinfunction "PB11_25") (pintype "passive"))
    )
    (net (code "60") (name "unconnected-(U6-PB12-Pad26)") (class "Default")
      (node (ref "U6") (pin "26") (pinfunction "PB12_26") (pintype "passive"))
    )
    (net (code "61") (name "unconnected-(U6-PB14-Pad28)") (class "Default")
      (node (ref "U6") (pin "28") (pinfunction "PB14_28") (pintype "passive"))
    )
    (net (code "62") (name "unconnected-(U6-PB15-Pad29)") (class "Default")
      (node (ref "U6") (pin "29") (pinfunction "PB15_29") (pintype "passive"))
    )
    (net (code "63") (name "unconnected-(U6-PC13-Pad2)") (class "Default")
      (node (ref "U6") (pin "2") (pinfunction "PC13_2") (pintype "passive"))
    )
    (net (code "64") (name "unconnected-(U6-PC14-OSC32_IN-Pad3)") (class "Default")
      (node (ref "U6") (pin "3") (pinfunction "PC14-OSC32_IN_3") (pintype "passive"))
    )
    (net (code "65") (name "unconnected-(U6-PC15-OSC32_OUT-Pad4)") (class "Default")
      (node (ref "U6") (pin "4") (pinfunction "PC15-OSC32_OUT_4") (pintype "passive"))
    )
    (net (code "66") (name "unconnected-(USB1-CC1-PadA5)") (class "Default")
      (node (ref "USB1") (pin "A5") (pinfunction "CC1_A5") (pintype "passive"))
    )
    (net (code "67") (name "unconnected-(USB1-CC2-PadB5)") (class "Default")
      (node (ref "USB1") (pin "B5") (pinfunction "CC2_B5") (pintype "passive"))
    )
    (net (code "68") (name "unconnected-(USB1-SBU1-PadA8)") (class "Default")
      (node (ref "USB1") (pin "A8") (pinfunction "SBU1_A8") (pintype "passive"))
    )
    (net (code "69") (name "unconnected-(USB1-SBU2-PadB8)") (class "Default")
      (node (ref "USB1") (pin "B8") (pinfunction "SBU2_B8") (pintype "passive"))
    )
  )
)
